# PCB-TLY-JACK-MEGA.net
KiCad netlist of a schematic drawn in EAGLE
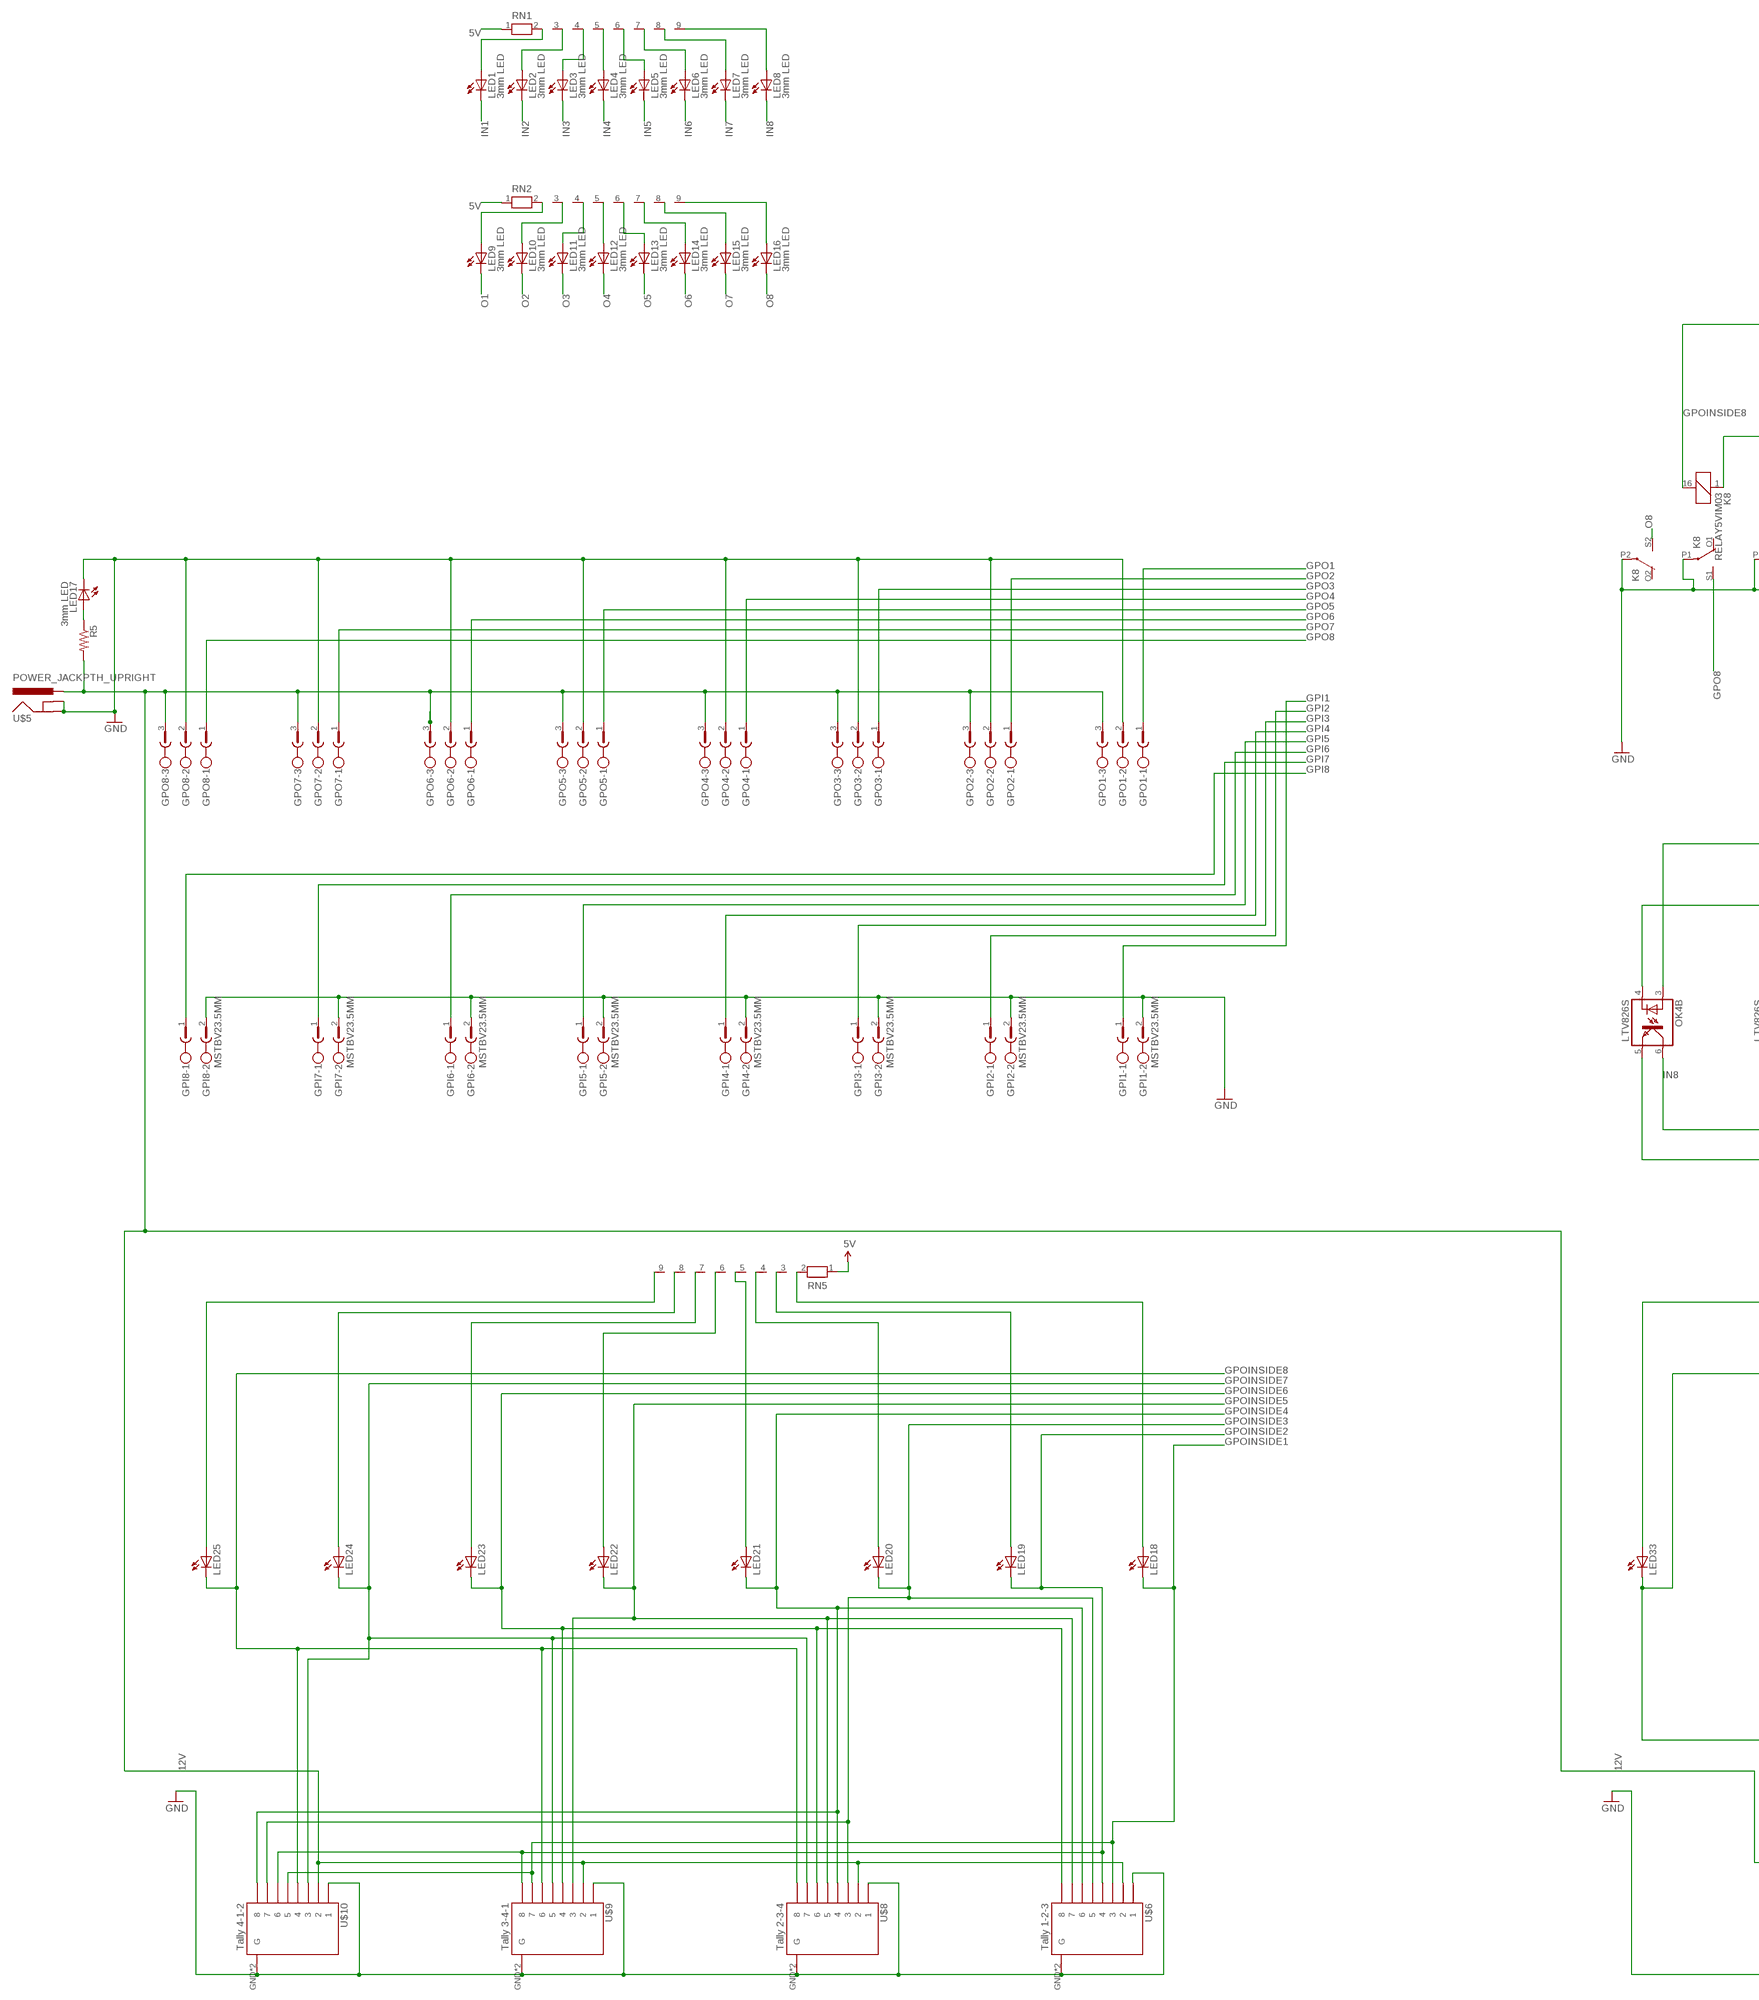
[diagram p0: schematic, sheet 1, part 1 of 2]
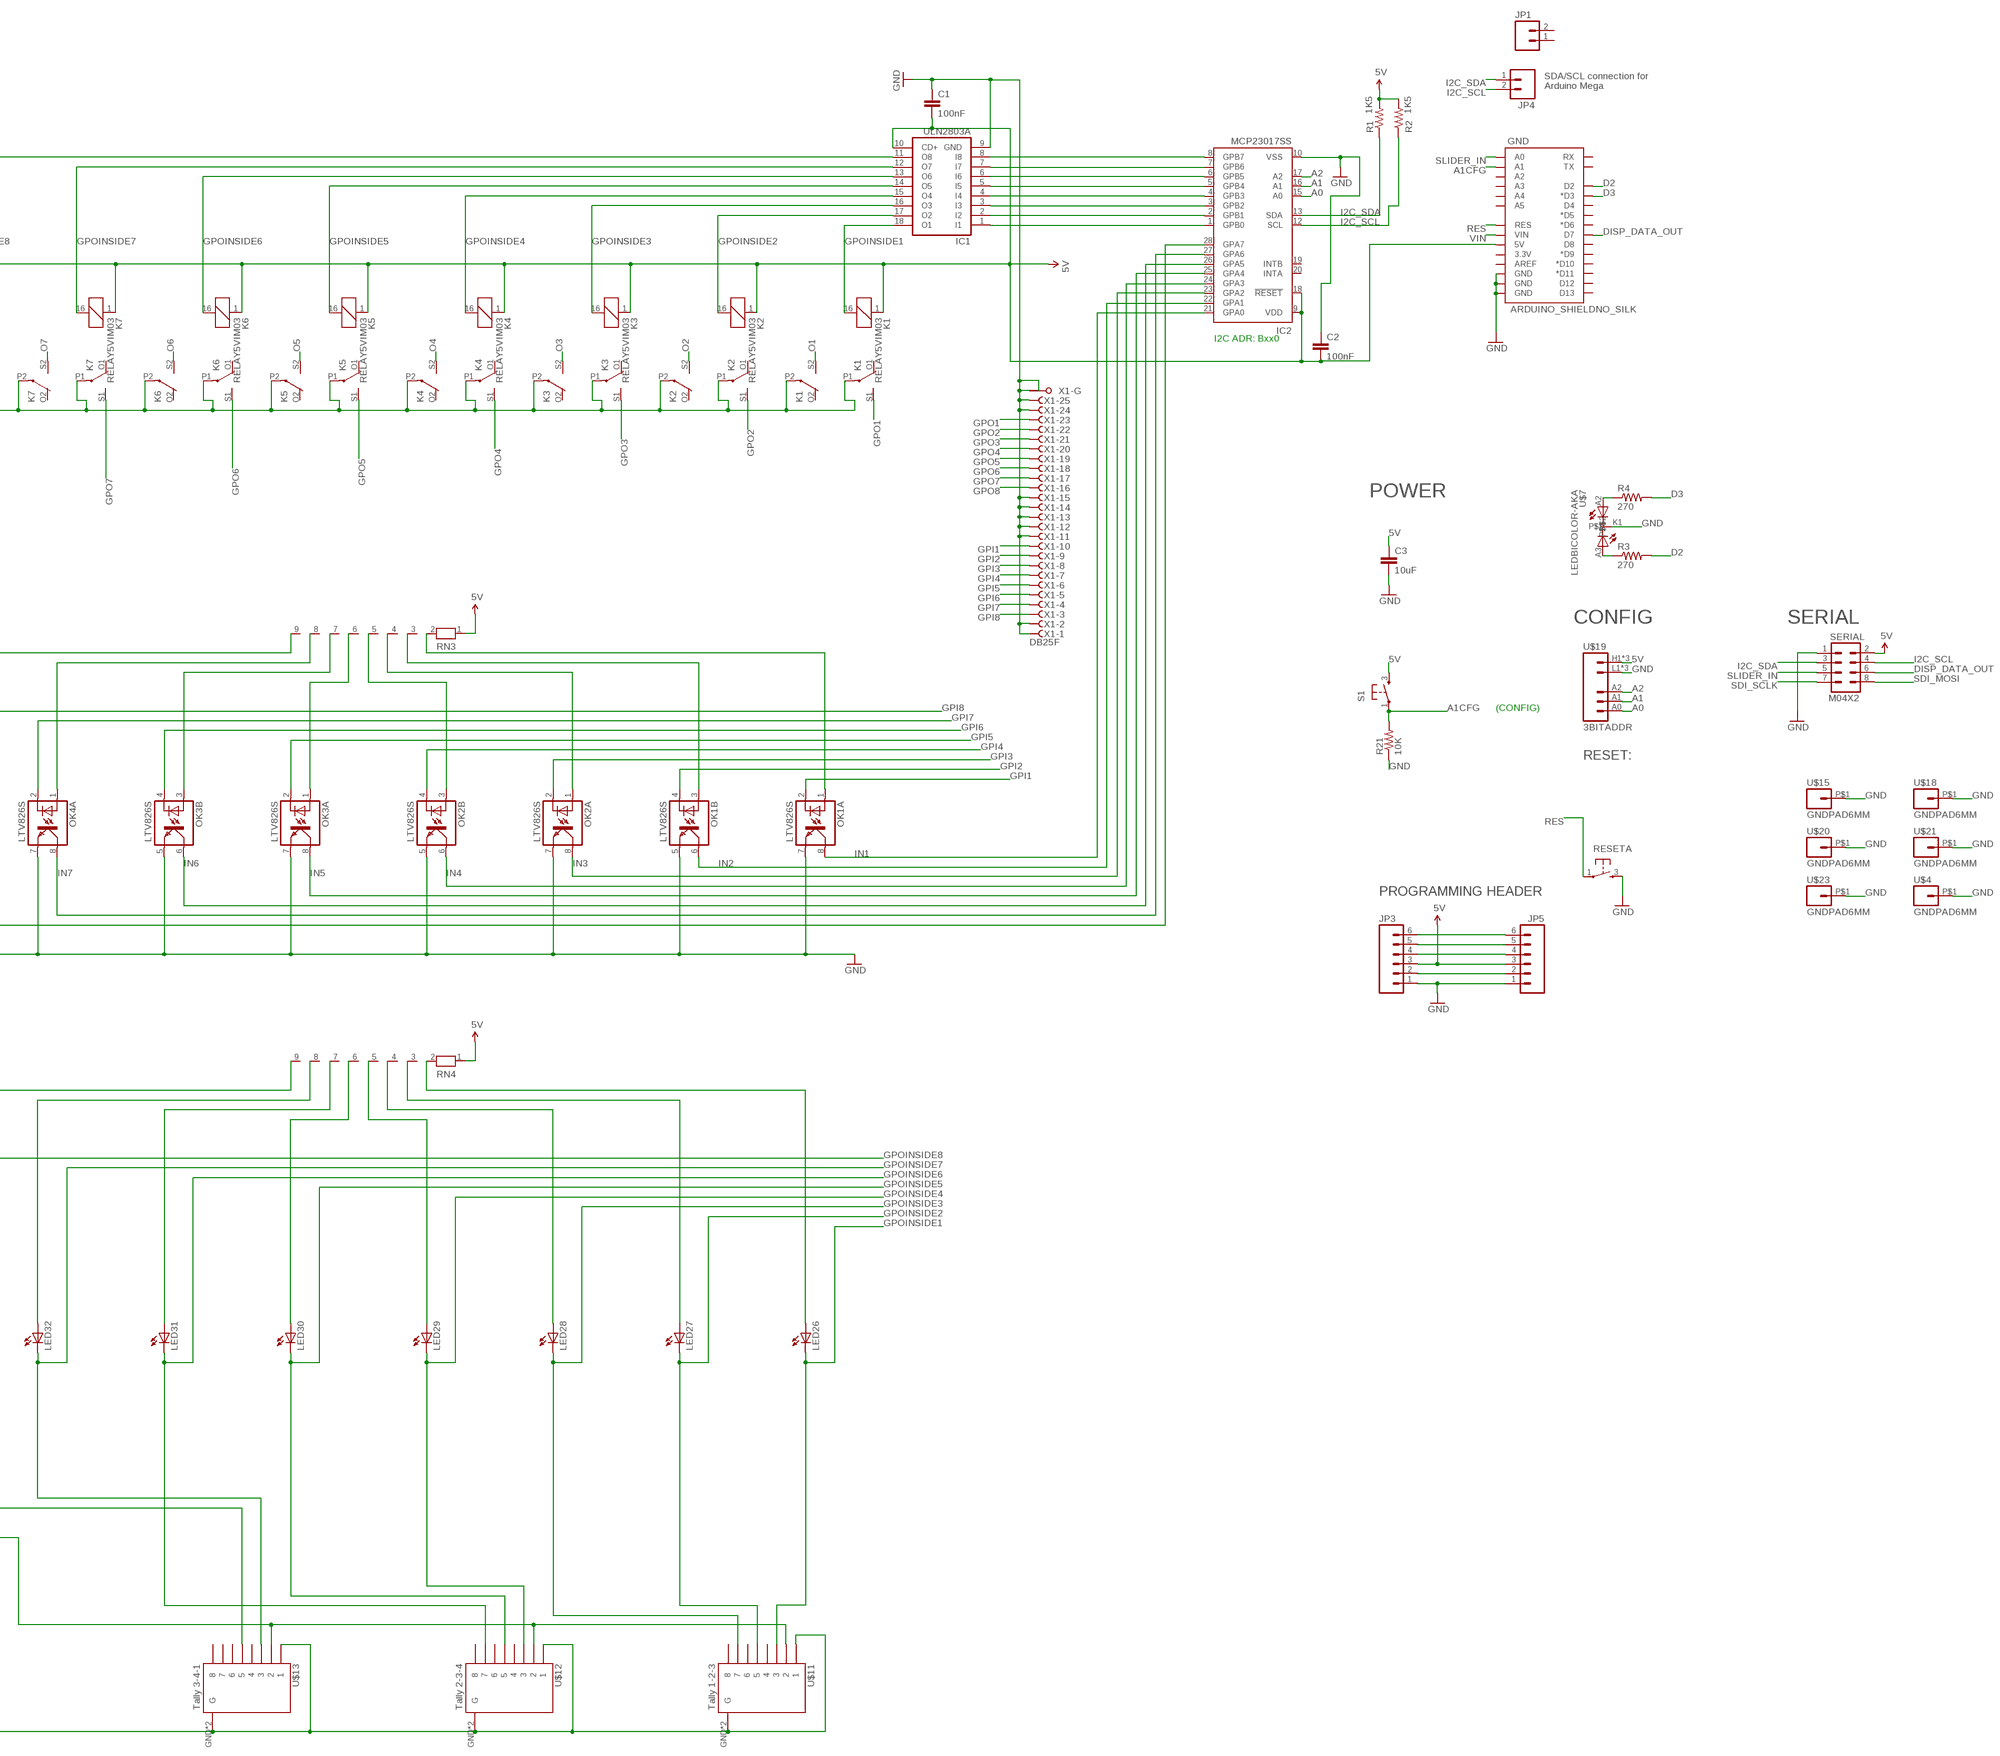
[diagram p1: schematic, sheet 1, part 2 of 2]

(export (version "E")
  (design (tool "Eeschema 10.0.6"))
  (components
    (comp (ref "C1")
      (value "100nF")
      (footprint "eagle-import:0805")
      (libsource (lib "eagle-import") (part "CAP0805"))
    )
    (comp (ref "C2")
      (value "100nF")
      (footprint "eagle-import:0603-CAP")
      (libsource (lib "eagle-import") (part "CAP0603-CAP"))
    )
    (comp (ref "C3")
      (value "10uF")
      (footprint "eagle-import:0805")
      (libsource (lib "eagle-import") (part "CAP0805"))
    )
    (comp (ref "GND")
      (value "ARDUINO_SHIELDNO_SILK")
      (footprint "eagle-import:DUEMILANOVE_VIAS")
      (libsource (lib "eagle-import") (part "ARDUINO_SHIELDNO_SILK"))
    )
    (comp (ref "GPI1")
      (value "MSTBV23.5MM")
      (footprint "eagle-import:MSTBV2-3.5")
      (libsource (lib "eagle-import") (part "MSTBV23.5MM"))
    )
    (comp (ref "GPI2")
      (value "MSTBV23.5MM")
      (footprint "eagle-import:MSTBV2-3.5")
      (libsource (lib "eagle-import") (part "MSTBV23.5MM"))
    )
    (comp (ref "GPI3")
      (value "MSTBV23.5MM")
      (footprint "eagle-import:MSTBV2-3.5")
      (libsource (lib "eagle-import") (part "MSTBV23.5MM"))
    )
    (comp (ref "GPI4")
      (value "MSTBV23.5MM")
      (footprint "eagle-import:MSTBV2-3.5")
      (libsource (lib "eagle-import") (part "MSTBV23.5MM"))
    )
    (comp (ref "GPI5")
      (value "MSTBV23.5MM")
      (footprint "eagle-import:MSTBV2-3.5")
      (libsource (lib "eagle-import") (part "MSTBV23.5MM"))
    )
    (comp (ref "GPI6")
      (value "MSTBV23.5MM")
      (footprint "eagle-import:MSTBV2-3.5")
      (libsource (lib "eagle-import") (part "MSTBV23.5MM"))
    )
    (comp (ref "GPI7")
      (value "MSTBV23.5MM")
      (footprint "eagle-import:MSTBV2-3.5")
      (libsource (lib "eagle-import") (part "MSTBV23.5MM"))
    )
    (comp (ref "GPI8")
      (value "MSTBV23.5MM")
      (footprint "eagle-import:MSTBV2-3.5")
      (libsource (lib "eagle-import") (part "MSTBV23.5MM"))
    )
    (comp (ref "GPO1")
      (value "CON1")
      (footprint "eagle-import:MSTBV3-3.5")
      (libsource (lib "eagle-import") (part "MSTBV33.5MM"))
    )
    (comp (ref "GPO2")
      (value "CON1")
      (footprint "eagle-import:MSTBV3-3.5")
      (libsource (lib "eagle-import") (part "MSTBV33.5MM"))
    )
    (comp (ref "GPO3")
      (value "CON1")
      (footprint "eagle-import:MSTBV3-3.5")
      (libsource (lib "eagle-import") (part "MSTBV33.5MM"))
    )
    (comp (ref "GPO4")
      (value "CON1")
      (footprint "eagle-import:MSTBV3-3.5")
      (libsource (lib "eagle-import") (part "MSTBV33.5MM"))
    )
    (comp (ref "GPO5")
      (value "CON1")
      (footprint "eagle-import:MSTBV3-3.5")
      (libsource (lib "eagle-import") (part "MSTBV33.5MM"))
    )
    (comp (ref "GPO6")
      (value "CON1")
      (footprint "eagle-import:MSTBV3-3.5")
      (libsource (lib "eagle-import") (part "MSTBV33.5MM"))
    )
    (comp (ref "GPO7")
      (value "CON1")
      (footprint "eagle-import:MSTBV3-3.5")
      (libsource (lib "eagle-import") (part "MSTBV33.5MM"))
    )
    (comp (ref "GPO8")
      (value "CON1")
      (footprint "eagle-import:MSTBV3-3.5")
      (libsource (lib "eagle-import") (part "MSTBV33.5MM"))
    )
    (comp (ref "IC1")
      (value "ULN2803A")
      (footprint "eagle-import:SO18W")
      (libsource (lib "eagle-import") (part "ULN2803ASO18W"))
    )
    (comp (ref "IC2")
      (value "MCP23017SS")
      (footprint "eagle-import:SSOP28")
      (fields (field (name "MF") "MICROCHIP") (field (name "MPN") "MCP23017-E/SS"))
      (libsource (lib "eagle-import") (part "MCP23017SS"))
    )
    (comp (ref "JP1")
      (value "M02PTH")
      (footprint "eagle-import:1X02")
      (libsource (lib "eagle-import") (part "M02PTH"))
    )
    (comp (ref "JP3")
      (value "M06POLAR")
      (footprint "eagle-import:MOLEX-1X6")
      (libsource (lib "eagle-import") (part "M06POLAR"))
    )
    (comp (ref "JP4")
      (value "M02PTH")
      (footprint "eagle-import:1X02")
      (libsource (lib "eagle-import") (part "M02PTH"))
    )
    (comp (ref "JP5")
      (value "M06POLAR")
      (footprint "eagle-import:MOLEX-1X6")
      (libsource (lib "eagle-import") (part "M06POLAR"))
    )
    (comp (ref "K1")
      (value "RELAY5VIM03")
      (footprint "eagle-import:DS2Y")
      (libsource (lib "eagle-import") (part "RELAY5VIM03"))
    )
    (comp (ref "K2")
      (value "RELAY5VIM03")
      (footprint "eagle-import:DS2Y")
      (libsource (lib "eagle-import") (part "RELAY5VIM03"))
    )
    (comp (ref "K3")
      (value "RELAY5VIM03")
      (footprint "eagle-import:DS2Y")
      (libsource (lib "eagle-import") (part "RELAY5VIM03"))
    )
    (comp (ref "K4")
      (value "RELAY5VIM03")
      (footprint "eagle-import:DS2Y")
      (libsource (lib "eagle-import") (part "RELAY5VIM03"))
    )
    (comp (ref "K5")
      (value "RELAY5VIM03")
      (footprint "eagle-import:DS2Y")
      (libsource (lib "eagle-import") (part "RELAY5VIM03"))
    )
    (comp (ref "K6")
      (value "RELAY5VIM03")
      (footprint "eagle-import:DS2Y")
      (libsource (lib "eagle-import") (part "RELAY5VIM03"))
    )
    (comp (ref "K7")
      (value "RELAY5VIM03")
      (footprint "eagle-import:DS2Y")
      (libsource (lib "eagle-import") (part "RELAY5VIM03"))
    )
    (comp (ref "K8")
      (value "RELAY5VIM03")
      (footprint "eagle-import:DS2Y")
      (libsource (lib "eagle-import") (part "RELAY5VIM03"))
    )
    (comp (ref "LED1")
      (value "3mm LED")
      (footprint "eagle-import:LED3MM")
      (libsource (lib "eagle-import") (part "LED3MM"))
    )
    (comp (ref "LED2")
      (value "3mm LED")
      (footprint "eagle-import:LED3MM")
      (libsource (lib "eagle-import") (part "LED3MM"))
    )
    (comp (ref "LED3")
      (value "3mm LED")
      (footprint "eagle-import:LED3MM")
      (libsource (lib "eagle-import") (part "LED3MM"))
    )
    (comp (ref "LED4")
      (value "3mm LED")
      (footprint "eagle-import:LED3MM")
      (libsource (lib "eagle-import") (part "LED3MM"))
    )
    (comp (ref "LED5")
      (value "3mm LED")
      (footprint "eagle-import:LED3MM")
      (libsource (lib "eagle-import") (part "LED3MM"))
    )
    (comp (ref "LED6")
      (value "3mm LED")
      (footprint "eagle-import:LED3MM")
      (libsource (lib "eagle-import") (part "LED3MM"))
    )
    (comp (ref "LED7")
      (value "3mm LED")
      (footprint "eagle-import:LED3MM")
      (libsource (lib "eagle-import") (part "LED3MM"))
    )
    (comp (ref "LED8")
      (value "3mm LED")
      (footprint "eagle-import:LED3MM")
      (libsource (lib "eagle-import") (part "LED3MM"))
    )
    (comp (ref "LED9")
      (value "3mm LED")
      (footprint "eagle-import:LED3MM")
      (libsource (lib "eagle-import") (part "LED3MM"))
    )
    (comp (ref "LED10")
      (value "3mm LED")
      (footprint "eagle-import:LED3MM")
      (libsource (lib "eagle-import") (part "LED3MM"))
    )
    (comp (ref "LED11")
      (value "3mm LED")
      (footprint "eagle-import:LED3MM")
      (libsource (lib "eagle-import") (part "LED3MM"))
    )
    (comp (ref "LED12")
      (value "3mm LED")
      (footprint "eagle-import:LED3MM")
      (libsource (lib "eagle-import") (part "LED3MM"))
    )
    (comp (ref "LED13")
      (value "3mm LED")
      (footprint "eagle-import:LED3MM")
      (libsource (lib "eagle-import") (part "LED3MM"))
    )
    (comp (ref "LED14")
      (value "3mm LED")
      (footprint "eagle-import:LED3MM")
      (libsource (lib "eagle-import") (part "LED3MM"))
    )
    (comp (ref "LED15")
      (value "3mm LED")
      (footprint "eagle-import:LED3MM")
      (libsource (lib "eagle-import") (part "LED3MM"))
    )
    (comp (ref "LED16")
      (value "3mm LED")
      (footprint "eagle-import:LED3MM")
      (libsource (lib "eagle-import") (part "LED3MM"))
    )
    (comp (ref "LED17")
      (value "3mm LED")
      (footprint "eagle-import:LED3MM")
      (libsource (lib "eagle-import") (part "LED3MM"))
    )
    (comp (ref "LED18")
      (value "LED3MM")
      (footprint "eagle-import:LED3MM")
      (libsource (lib "eagle-import") (part "led_LED3MM"))
    )
    (comp (ref "LED19")
      (value "LED3MM")
      (footprint "eagle-import:LED3MM")
      (libsource (lib "eagle-import") (part "led_LED3MM"))
    )
    (comp (ref "LED20")
      (value "LED3MM")
      (footprint "eagle-import:LED3MM")
      (libsource (lib "eagle-import") (part "led_LED3MM"))
    )
    (comp (ref "LED21")
      (value "LED3MM")
      (footprint "eagle-import:LED3MM")
      (libsource (lib "eagle-import") (part "led_LED3MM"))
    )
    (comp (ref "LED22")
      (value "LED3MM")
      (footprint "eagle-import:LED3MM")
      (libsource (lib "eagle-import") (part "led_LED3MM"))
    )
    (comp (ref "LED23")
      (value "LED3MM")
      (footprint "eagle-import:LED3MM")
      (libsource (lib "eagle-import") (part "led_LED3MM"))
    )
    (comp (ref "LED24")
      (value "LED3MM")
      (footprint "eagle-import:LED3MM")
      (libsource (lib "eagle-import") (part "led_LED3MM"))
    )
    (comp (ref "LED25")
      (value "LED3MM")
      (footprint "eagle-import:LED3MM")
      (libsource (lib "eagle-import") (part "led_LED3MM"))
    )
    (comp (ref "LED26")
      (value "LED3MM")
      (footprint "eagle-import:LED3MM")
      (libsource (lib "eagle-import") (part "led_LED3MM"))
    )
    (comp (ref "LED27")
      (value "LED3MM")
      (footprint "eagle-import:LED3MM")
      (libsource (lib "eagle-import") (part "led_LED3MM"))
    )
    (comp (ref "LED28")
      (value "LED3MM")
      (footprint "eagle-import:LED3MM")
      (libsource (lib "eagle-import") (part "led_LED3MM"))
    )
    (comp (ref "LED29")
      (value "LED3MM")
      (footprint "eagle-import:LED3MM")
      (libsource (lib "eagle-import") (part "led_LED3MM"))
    )
    (comp (ref "LED30")
      (value "LED3MM")
      (footprint "eagle-import:LED3MM")
      (libsource (lib "eagle-import") (part "led_LED3MM"))
    )
    (comp (ref "LED31")
      (value "LED3MM")
      (footprint "eagle-import:LED3MM")
      (libsource (lib "eagle-import") (part "led_LED3MM"))
    )
    (comp (ref "LED32")
      (value "LED3MM")
      (footprint "eagle-import:LED3MM")
      (libsource (lib "eagle-import") (part "led_LED3MM"))
    )
    (comp (ref "LED33")
      (value "LED3MM")
      (footprint "eagle-import:LED3MM")
      (libsource (lib "eagle-import") (part "led_LED3MM"))
    )
    (comp (ref "OK1")
      (value "LTV826S")
      (footprint "eagle-import:DIL8-SMD")
      (libsource (lib "eagle-import") (part "LTV826S"))
    )
    (comp (ref "OK2")
      (value "LTV826S")
      (footprint "eagle-import:DIL8-SMD")
      (libsource (lib "eagle-import") (part "LTV826S"))
    )
    (comp (ref "OK3")
      (value "LTV826S")
      (footprint "eagle-import:DIL8-SMD")
      (libsource (lib "eagle-import") (part "LTV826S"))
    )
    (comp (ref "OK4")
      (value "LTV826S")
      (footprint "eagle-import:DIL8-SMD")
      (libsource (lib "eagle-import") (part "LTV826S"))
    )
    (comp (ref "R1")
      (value "1K5")
      (footprint "eagle-import:0603-RES")
      (libsource (lib "eagle-import") (part "RESISTOR0603-RES"))
    )
    (comp (ref "R2")
      (value "1K5")
      (footprint "eagle-import:0603-RES")
      (libsource (lib "eagle-import") (part "RESISTOR0603-RES"))
    )
    (comp (ref "R3")
      (value "270")
      (footprint "eagle-import:0603-RES")
      (libsource (lib "eagle-import") (part "RESISTOR0603-RES"))
    )
    (comp (ref "R4")
      (value "270")
      (footprint "eagle-import:0603-RES")
      (libsource (lib "eagle-import") (part "RESISTOR0603-RES"))
    )
    (comp (ref "R5")
      (value "RESISTOR0603-RES")
      (footprint "eagle-import:0603-RES")
      (libsource (lib "eagle-import") (part "RESISTOR0603-RES"))
    )
    (comp (ref "R21")
      (value "10K")
      (footprint "eagle-import:0603-RES")
      (libsource (lib "eagle-import") (part "RESISTOR0603-RES"))
    )
    (comp (ref "RESETA")
      (value "TAC_SWITCH")
      (footprint "eagle-import:PUSHBUTTON")
      (libsource (lib "eagle-import") (part "TAC_SWITCH"))
    )
    (comp (ref "RN1")
      (value "RN08")
      (footprint "eagle-import:RN-9")
      (libsource (lib "eagle-import") (part "RN08"))
    )
    (comp (ref "RN2")
      (value "RN08")
      (footprint "eagle-import:RN-9")
      (libsource (lib "eagle-import") (part "RN08"))
    )
    (comp (ref "RN3")
      (value "RN08")
      (footprint "eagle-import:RN-9")
      (libsource (lib "eagle-import") (part "RN08"))
    )
    (comp (ref "RN4")
      (value "RN08")
      (footprint "eagle-import:RN-9")
      (libsource (lib "eagle-import") (part "RN08"))
    )
    (comp (ref "RN5")
      (value "RN08")
      (footprint "eagle-import:RN-9")
      (libsource (lib "eagle-import") (part "RN08"))
    )
    (comp (ref "S1")
      (value "TAC_SWITCH")
      (footprint "eagle-import:PUSHBUTTON")
      (libsource (lib "eagle-import") (part "TAC_SWITCH"))
    )
    (comp (ref "SERIAL")
      (value "M04X2")
      (footprint "eagle-import:2X4")
      (libsource (lib "eagle-import") (part "M04X2"))
    )
    (comp (ref "U$4")
      (value "GNDPAD6MM")
      (footprint "eagle-import:3.2MMPAD6MM")
      (libsource (lib "eagle-import") (part "GNDPAD6MM"))
    )
    (comp (ref "U$5")
      (value "POWER_JACKPTH_UPRIGHT")
      (footprint "eagle-import:POWER_JACK_PTH_UPRIGHT")
      (libsource (lib "eagle-import") (part "POWER_JACKPTH_UPRIGHT"))
    )
    (comp (ref "U$6")
      (value "Tally 1-2-3")
      (footprint "eagle-import:RJ45-8_GND_UPRIGHT")
      (libsource (lib "eagle-import") (part "RJ45-8_GNDUPRIGHT"))
    )
    (comp (ref "U$7")
      (value "LEDBICOLOR-AKA")
      (footprint "eagle-import:LED5MM-BICOLOR")
      (libsource (lib "eagle-import") (part "LEDBICOLOR-AKA"))
    )
    (comp (ref "U$8")
      (value "Tally 2-3-4")
      (footprint "eagle-import:RJ45-8_GND_UPRIGHT")
      (libsource (lib "eagle-import") (part "RJ45-8_GNDUPRIGHT"))
    )
    (comp (ref "U$9")
      (value "Tally 3-4-1")
      (footprint "eagle-import:RJ45-8_GND_UPRIGHT")
      (libsource (lib "eagle-import") (part "RJ45-8_GNDUPRIGHT"))
    )
    (comp (ref "U$10")
      (value "Tally 4-1-2")
      (footprint "eagle-import:RJ45-8_GND_UPRIGHT")
      (libsource (lib "eagle-import") (part "RJ45-8_GNDUPRIGHT"))
    )
    (comp (ref "U$11")
      (value "Tally 1-2-3")
      (footprint "eagle-import:RJ45-8_GND_UPRIGHT")
      (libsource (lib "eagle-import") (part "RJ45-8_GNDUPRIGHT"))
    )
    (comp (ref "U$12")
      (value "Tally 2-3-4")
      (footprint "eagle-import:RJ45-8_GND_UPRIGHT")
      (libsource (lib "eagle-import") (part "RJ45-8_GNDUPRIGHT"))
    )
    (comp (ref "U$13")
      (value "Tally 3-4-1")
      (footprint "eagle-import:RJ45-8_GND_UPRIGHT")
      (libsource (lib "eagle-import") (part "RJ45-8_GNDUPRIGHT"))
    )
    (comp (ref "U$15")
      (value "GNDPAD6MM")
      (footprint "eagle-import:3.2MMPAD6MM")
      (libsource (lib "eagle-import") (part "GNDPAD6MM"))
    )
    (comp (ref "U$18")
      (value "GNDPAD6MM")
      (footprint "eagle-import:3.2MMPAD6MM")
      (libsource (lib "eagle-import") (part "GNDPAD6MM"))
    )
    (comp (ref "U$19")
      (value "3BITADDR")
      (footprint "eagle-import:3BITADDR")
      (libsource (lib "eagle-import") (part "3BITADDR"))
    )
    (comp (ref "U$20")
      (value "GNDPAD6MM")
      (footprint "eagle-import:3.2MMPAD6MM")
      (libsource (lib "eagle-import") (part "GNDPAD6MM"))
    )
    (comp (ref "U$21")
      (value "GNDPAD6MM")
      (footprint "eagle-import:3.2MMPAD6MM")
      (libsource (lib "eagle-import") (part "GNDPAD6MM"))
    )
    (comp (ref "U$23")
      (value "GNDPAD6MM")
      (footprint "eagle-import:3.2MMPAD6MM")
      (libsource (lib "eagle-import") (part "GNDPAD6MM"))
    )
    (comp (ref "X1")
      (value "DB25F")
      (footprint "eagle-import:F25HP")
      (libsource (lib "eagle-import") (part "F25HPS"))
    )
  )
  (nets
    (net (code "1") (name "5V") (class "Default")
      (node (ref "C1") (pin "2") (pinfunction "2_2") (pintype "passive"))
      (node (ref "C2") (pin "2") (pinfunction "2_2") (pintype "passive"))
      (node (ref "C3") (pin "1") (pinfunction "1_1") (pintype "passive"))
      (node (ref "GND") (pin "5V") (pinfunction "5V_5V") (pintype "bidirectional"))
      (node (ref "IC1") (pin "10") (pinfunction "CD+_10") (pintype "passive"))
      (node (ref "IC2") (pin "18") (pinfunction "~{RESET}_18") (pintype "input"))
      (node (ref "IC2") (pin "9") (pinfunction "VDD_9") (pintype "power_in"))
      (node (ref "JP3") (pin "3") (pinfunction "3_3") (pintype "passive"))
      (node (ref "JP5") (pin "3") (pinfunction "3_3") (pintype "passive"))
      (node (ref "K1") (pin "1") (pinfunction "1_1") (pintype "passive"))
      (node (ref "K2") (pin "1") (pinfunction "1_1") (pintype "passive"))
      (node (ref "K3") (pin "1") (pinfunction "1_1") (pintype "passive"))
      (node (ref "K4") (pin "1") (pinfunction "1_1") (pintype "passive"))
      (node (ref "K5") (pin "1") (pinfunction "1_1") (pintype "passive"))
      (node (ref "K6") (pin "1") (pinfunction "1_1") (pintype "passive"))
      (node (ref "K7") (pin "1") (pinfunction "1_1") (pintype "passive"))
      (node (ref "K8") (pin "1") (pinfunction "1_1") (pintype "passive"))
      (node (ref "R1") (pin "2") (pinfunction "2_2") (pintype "passive"))
      (node (ref "R2") (pin "2") (pinfunction "2_2") (pintype "passive"))
      (node (ref "RN1") (pin "1") (pinfunction "1_1") (pintype "passive"))
      (node (ref "RN2") (pin "1") (pinfunction "1_1") (pintype "passive"))
      (node (ref "RN3") (pin "1") (pinfunction "1_1") (pintype "passive"))
      (node (ref "RN4") (pin "1") (pinfunction "1_1") (pintype "passive"))
      (node (ref "RN5") (pin "1") (pinfunction "1_1") (pintype "passive"))
      (node (ref "S1") (pin "3") (pinfunction "3_3") (pintype "passive"))
      (node (ref "SERIAL") (pin "2") (pinfunction "2_2") (pintype "passive"))
      (node (ref "U$19") (pin "H1") (pinfunction "VCC_H1") (pintype "passive"))
      (node (ref "U$19") (pin "H2") (pinfunction "VCC_H2") (pintype "passive"))
      (node (ref "U$19") (pin "H3") (pinfunction "VCC_H3") (pintype "passive"))
    )
    (net (code "2") (name "12V") (class "Default")
      (node (ref "GPO1") (pin "3") (pinfunction "1_3") (pintype "passive"))
      (node (ref "GPO2") (pin "3") (pinfunction "1_3") (pintype "passive"))
      (node (ref "GPO3") (pin "3") (pinfunction "1_3") (pintype "passive"))
      (node (ref "GPO4") (pin "3") (pinfunction "1_3") (pintype "passive"))
      (node (ref "GPO5") (pin "3") (pinfunction "1_3") (pintype "passive"))
      (node (ref "GPO6") (pin "3") (pinfunction "1_3") (pintype "passive"))
      (node (ref "GPO7") (pin "3") (pinfunction "1_3") (pintype "passive"))
      (node (ref "GPO8") (pin "3") (pinfunction "1_3") (pintype "passive"))
      (node (ref "R5") (pin "2") (pinfunction "2_2") (pintype "passive"))
      (node (ref "U$10") (pin "2") (pinfunction "2_2") (pintype "bidirectional"))
      (node (ref "U$11") (pin "2") (pinfunction "2_2") (pintype "bidirectional"))
      (node (ref "U$12") (pin "2") (pinfunction "2_2") (pintype "bidirectional"))
      (node (ref "U$13") (pin "2") (pinfunction "2_2") (pintype "bidirectional"))
      (node (ref "U$5") (pin "PWR") (pinfunction "PWR_PWR") (pintype "bidirectional"))
      (node (ref "U$6") (pin "2") (pinfunction "2_2") (pintype "bidirectional"))
      (node (ref "U$8") (pin "2") (pinfunction "2_2") (pintype "bidirectional"))
      (node (ref "U$9") (pin "2") (pinfunction "2_2") (pintype "bidirectional"))
    )
    (net (code "3") (name "A0") (class "Default")
      (node (ref "IC2") (pin "15") (pinfunction "A0_15") (pintype "input"))
      (node (ref "U$19") (pin "A0") (pinfunction "A0_A0") (pintype "passive"))
    )
    (net (code "4") (name "A1") (class "Default")
      (node (ref "IC2") (pin "16") (pinfunction "A1_16") (pintype "input"))
      (node (ref "U$19") (pin "A1") (pinfunction "A1_A1") (pintype "passive"))
    )
    (net (code "5") (name "A1CFG") (class "Default")
      (node (ref "GND") (pin "A1") (pinfunction "A1_A1") (pintype "bidirectional"))
      (node (ref "R21") (pin "2") (pinfunction "2_2") (pintype "passive"))
      (node (ref "S1") (pin "1") (pinfunction "1_1") (pintype "passive"))
    )
    (net (code "6") (name "A2") (class "Default")
      (node (ref "IC2") (pin "17") (pinfunction "A2_17") (pintype "input"))
      (node (ref "U$19") (pin "A2") (pinfunction "A2_A2") (pintype "passive"))
    )
    (net (code "7") (name "D2") (class "Default")
      (node (ref "GND") (pin "D2") (pinfunction "D2_D2") (pintype "bidirectional"))
      (node (ref "R3") (pin "2") (pinfunction "2_2") (pintype "passive"))
    )
    (net (code "8") (name "D3") (class "Default")
      (node (ref "GND") (pin "D3") (pinfunction "*D3_D3") (pintype "bidirectional"))
      (node (ref "R4") (pin "2") (pinfunction "2_2") (pintype "passive"))
    )
    (net (code "9") (name "DISP_DATA_OUT") (class "Default")
      (node (ref "GND") (pin "D7") (pinfunction "D7_D7") (pintype "bidirectional"))
      (node (ref "SERIAL") (pin "6") (pinfunction "6_6") (pintype "passive"))
    )
    (net (code "10") (name "GND") (class "Default")
      (node (ref "C1") (pin "1") (pinfunction "1_1") (pintype "passive"))
      (node (ref "C2") (pin "1") (pinfunction "1_1") (pintype "passive"))
      (node (ref "C3") (pin "2") (pinfunction "2_2") (pintype "passive"))
      (node (ref "GND") (pin "GND@0") (pinfunction "GND_GND@0") (pintype "bidirectional"))
      (node (ref "GND") (pin "GND@1") (pinfunction "GND_GND@1") (pintype "bidirectional"))
      (node (ref "GND") (pin "GND@2") (pinfunction "GND_GND@2") (pintype "bidirectional"))
      (node (ref "GPI1") (pin "2") (pinfunction "1_2") (pintype "passive"))
      (node (ref "GPI2") (pin "2") (pinfunction "1_2") (pintype "passive"))
      (node (ref "GPI3") (pin "2") (pinfunction "1_2") (pintype "passive"))
      (node (ref "GPI4") (pin "2") (pinfunction "1_2") (pintype "passive"))
      (node (ref "GPI5") (pin "2") (pinfunction "1_2") (pintype "passive"))
      (node (ref "GPI6") (pin "2") (pinfunction "1_2") (pintype "passive"))
      (node (ref "GPI7") (pin "2") (pinfunction "1_2") (pintype "passive"))
      (node (ref "GPI8") (pin "2") (pinfunction "1_2") (pintype "passive"))
      (node (ref "GPO1") (pin "2") (pinfunction "1_2") (pintype "passive"))
      (node (ref "GPO2") (pin "2") (pinfunction "1_2") (pintype "passive"))
      (node (ref "GPO3") (pin "2") (pinfunction "1_2") (pintype "passive"))
      (node (ref "GPO4") (pin "2") (pinfunction "1_2") (pintype "passive"))
      (node (ref "GPO5") (pin "2") (pinfunction "1_2") (pintype "passive"))
      (node (ref "GPO6") (pin "2") (pinfunction "1_2") (pintype "passive"))
      (node (ref "GPO7") (pin "2") (pinfunction "1_2") (pintype "passive"))
      (node (ref "GPO8") (pin "2") (pinfunction "1_2") (pintype "passive"))
      (node (ref "IC1") (pin "9") (pinfunction "GND_9") (pintype "power_in"))
      (node (ref "IC2") (pin "10") (pinfunction "VSS_10") (pintype "power_in"))
      (node (ref "JP3") (pin "1") (pinfunction "1_1") (pintype "passive"))
      (node (ref "JP5") (pin "1") (pinfunction "1_1") (pintype "passive"))
      (node (ref "K1") (pin "P1") (pinfunction "P_P1") (pintype "passive"))
      (node (ref "K1") (pin "P2") (pinfunction "P_P2") (pintype "passive"))
      (node (ref "K2") (pin "P1") (pinfunction "P_P1") (pintype "passive"))
      (node (ref "K2") (pin "P2") (pinfunction "P_P2") (pintype "passive"))
      (node (ref "K3") (pin "P1") (pinfunction "P_P1") (pintype "passive"))
      (node (ref "K3") (pin "P2") (pinfunction "P_P2") (pintype "passive"))
      (node (ref "K4") (pin "P1") (pinfunction "P_P1") (pintype "passive"))
      (node (ref "K4") (pin "P2") (pinfunction "P_P2") (pintype "passive"))
      (node (ref "K5") (pin "P1") (pinfunction "P_P1") (pintype "passive"))
      (node (ref "K5") (pin "P2") (pinfunction "P_P2") (pintype "passive"))
      (node (ref "K6") (pin "P1") (pinfunction "P_P1") (pintype "passive"))
      (node (ref "K6") (pin "P2") (pinfunction "P_P2") (pintype "passive"))
      (node (ref "K7") (pin "P1") (pinfunction "P_P1") (pintype "passive"))
      (node (ref "K7") (pin "P2") (pinfunction "P_P2") (pintype "passive"))
      (node (ref "K8") (pin "P1") (pinfunction "P_P1") (pintype "passive"))
      (node (ref "K8") (pin "P2") (pinfunction "P_P2") (pintype "passive"))
      (node (ref "LED17") (pin "K") (pinfunction "C_K") (pintype "passive"))
      (node (ref "OK1") (pin "5") (pinfunction "EMIT_5") (pintype "passive"))
      (node (ref "OK1") (pin "7") (pinfunction "EMIT_7") (pintype "passive"))
      (node (ref "OK2") (pin "5") (pinfunction "EMIT_5") (pintype "passive"))
      (node (ref "OK2") (pin "7") (pinfunction "EMIT_7") (pintype "passive"))
      (node (ref "OK3") (pin "5") (pinfunction "EMIT_5") (pintype "passive"))
      (node (ref "OK3") (pin "7") (pinfunction "EMIT_7") (pintype "passive"))
      (node (ref "OK4") (pin "5") (pinfunction "EMIT_5") (pintype "passive"))
      (node (ref "OK4") (pin "7") (pinfunction "EMIT_7") (pintype "passive"))
      (node (ref "R21") (pin "1") (pinfunction "1_1") (pintype "passive"))
      (node (ref "RESETA") (pin "3") (pinfunction "3_3") (pintype "passive"))
      (node (ref "SERIAL") (pin "1") (pinfunction "1_1") (pintype "passive"))
      (node (ref "U$10") (pin "1") (pinfunction "1_1") (pintype "bidirectional"))
      (node (ref "U$10") (pin "GND") (pinfunction "G_GND") (pintype "power_in"))
      (node (ref "U$10") (pin "GND1") (pinfunction "G_GND1") (pintype "power_in"))
      (node (ref "U$11") (pin "1") (pinfunction "1_1") (pintype "bidirectional"))
      (node (ref "U$11") (pin "GND") (pinfunction "G_GND") (pintype "power_in"))
      (node (ref "U$11") (pin "GND1") (pinfunction "G_GND1") (pintype "power_in"))
      (node (ref "U$12") (pin "1") (pinfunction "1_1") (pintype "bidirectional"))
      (node (ref "U$12") (pin "GND") (pinfunction "G_GND") (pintype "power_in"))
      (node (ref "U$12") (pin "GND1") (pinfunction "G_GND1") (pintype "power_in"))
      (node (ref "U$13") (pin "1") (pinfunction "1_1") (pintype "bidirectional"))
      (node (ref "U$13") (pin "GND") (pinfunction "G_GND") (pintype "power_in"))
      (node (ref "U$13") (pin "GND1") (pinfunction "G_GND1") (pintype "power_in"))
      (node (ref "U$15") (pin "P$1") (pinfunction "1_P$1") (pintype "passive"))
      (node (ref "U$18") (pin "P$1") (pinfunction "1_P$1") (pintype "passive"))
      (node (ref "U$19") (pin "L1") (pinfunction "GND_L1") (pintype "passive"))
      (node (ref "U$19") (pin "L2") (pinfunction "GND_L2") (pintype "passive"))
      (node (ref "U$19") (pin "L3") (pinfunction "GND_L3") (pintype "passive"))
      (node (ref "U$20") (pin "P$1") (pinfunction "1_P$1") (pintype "passive"))
      (node (ref "U$21") (pin "P$1") (pinfunction "1_P$1") (pintype "passive"))
      (node (ref "U$23") (pin "P$1") (pinfunction "1_P$1") (pintype "passive"))
      (node (ref "U$4") (pin "P$1") (pinfunction "1_P$1") (pintype "passive"))
      (node (ref "U$5") (pin "GND") (pinfunction "GND_GND") (pintype "bidirectional"))
      (node (ref "U$5") (pin "SHUNT") (pinfunction "GNDBREAK_SHUNT") (pintype "bidirectional"))
      (node (ref "U$6") (pin "1") (pinfunction "1_1") (pintype "bidirectional"))
      (node (ref "U$6") (pin "GND") (pinfunction "G_GND") (pintype "power_in"))
      (node (ref "U$6") (pin "GND1") (pinfunction "G_GND1") (pintype "power_in"))
      (node (ref "U$7") (pin "K1") (pinfunction "P$1_K1") (pintype "bidirectional"))
      (node (ref "U$8") (pin "1") (pinfunction "1_1") (pintype "bidirectional"))
      (node (ref "U$8") (pin "GND") (pinfunction "G_GND") (pintype "power_in"))
      (node (ref "U$8") (pin "GND1") (pinfunction "G_GND1") (pintype "power_in"))
      (node (ref "U$9") (pin "1") (pinfunction "1_1") (pintype "bidirectional"))
      (node (ref "U$9") (pin "GND") (pinfunction "G_GND") (pintype "power_in"))
      (node (ref "U$9") (pin "GND1") (pinfunction "G_GND1") (pintype "power_in"))
      (node (ref "X1") (pin "1") (pinfunction "F_1") (pintype "passive"))
      (node (ref "X1") (pin "11") (pinfunction "F_11") (pintype "passive"))
      (node (ref "X1") (pin "12") (pinfunction "F_12") (pintype "passive"))
      (node (ref "X1") (pin "13") (pinfunction "F_13") (pintype "passive"))
      (node (ref "X1") (pin "14") (pinfunction "F_14") (pintype "passive"))
      (node (ref "X1") (pin "15") (pinfunction "F_15") (pintype "passive"))
      (node (ref "X1") (pin "2") (pinfunction "F_2") (pintype "passive"))
      (node (ref "X1") (pin "24") (pinfunction "F_24") (pintype "passive"))
      (node (ref "X1") (pin "25") (pinfunction "F_25") (pintype "passive"))
      (node (ref "X1") (pin "G1") (pinfunction "G1_G1") (pintype "passive"))
      (node (ref "X1") (pin "G2") (pinfunction "G2_G2") (pintype "passive"))
    )
    (net (code "11") (name "GPI1") (class "Default")
      (node (ref "GPI1") (pin "1") (pinfunction "1_1") (pintype "passive"))
      (node (ref "OK1") (pin "2") (pinfunction "C_2") (pintype "passive"))
      (node (ref "X1") (pin "10") (pinfunction "F_10") (pintype "passive"))
    )
    (net (code "12") (name "GPI2") (class "Default")
      (node (ref "GPI2") (pin "1") (pinfunction "1_1") (pintype "passive"))
      (node (ref "OK1") (pin "4") (pinfunction "C_4") (pintype "passive"))
      (node (ref "X1") (pin "9") (pinfunction "F_9") (pintype "passive"))
    )
    (net (code "13") (name "GPI3") (class "Default")
      (node (ref "GPI3") (pin "1") (pinfunction "1_1") (pintype "passive"))
      (node (ref "OK2") (pin "2") (pinfunction "C_2") (pintype "passive"))
      (node (ref "X1") (pin "8") (pinfunction "F_8") (pintype "passive"))
    )
    (net (code "14") (name "GPI4") (class "Default")
      (node (ref "GPI4") (pin "1") (pinfunction "1_1") (pintype "passive"))
      (node (ref "OK2") (pin "4") (pinfunction "C_4") (pintype "passive"))
      (node (ref "X1") (pin "7") (pinfunction "F_7") (pintype "passive"))
    )
    (net (code "15") (name "GPI5") (class "Default")
      (node (ref "GPI5") (pin "1") (pinfunction "1_1") (pintype "passive"))
      (node (ref "OK3") (pin "2") (pinfunction "C_2") (pintype "passive"))
      (node (ref "X1") (pin "6") (pinfunction "F_6") (pintype "passive"))
    )
    (net (code "16") (name "GPI6") (class "Default")
      (node (ref "GPI6") (pin "1") (pinfunction "1_1") (pintype "passive"))
      (node (ref "OK3") (pin "4") (pinfunction "C_4") (pintype "passive"))
      (node (ref "X1") (pin "5") (pinfunction "F_5") (pintype "passive"))
    )
    (net (code "17") (name "GPI7") (class "Default")
      (node (ref "GPI7") (pin "1") (pinfunction "1_1") (pintype "passive"))
      (node (ref "OK4") (pin "2") (pinfunction "C_2") (pintype "passive"))
      (node (ref "X1") (pin "4") (pinfunction "F_4") (pintype "passive"))
    )
    (net (code "18") (name "GPI8") (class "Default")
      (node (ref "GPI8") (pin "1") (pinfunction "1_1") (pintype "passive"))
      (node (ref "OK4") (pin "4") (pinfunction "C_4") (pintype "passive"))
      (node (ref "X1") (pin "3") (pinfunction "F_3") (pintype "passive"))
    )
    (net (code "19") (name "GPO1") (class "Default")
      (node (ref "GPO1") (pin "1") (pinfunction "1_1") (pintype "passive"))
      (node (ref "K1") (pin "S1") (pinfunction "S_S1") (pintype "passive"))
      (node (ref "X1") (pin "23") (pinfunction "F_23") (pintype "passive"))
    )
    (net (code "20") (name "GPO2") (class "Default")
      (node (ref "GPO2") (pin "1") (pinfunction "1_1") (pintype "passive"))
      (node (ref "K2") (pin "S1") (pinfunction "S_S1") (pintype "passive"))
      (node (ref "X1") (pin "22") (pinfunction "F_22") (pintype "passive"))
    )
    (net (code "21") (name "GPO3") (class "Default")
      (node (ref "GPO3") (pin "1") (pinfunction "1_1") (pintype "passive"))
      (node (ref "K3") (pin "S1") (pinfunction "S_S1") (pintype "passive"))
      (node (ref "X1") (pin "21") (pinfunction "F_21") (pintype "passive"))
    )
    (net (code "22") (name "GPO4") (class "Default")
      (node (ref "GPO4") (pin "1") (pinfunction "1_1") (pintype "passive"))
      (node (ref "K4") (pin "S1") (pinfunction "S_S1") (pintype "passive"))
      (node (ref "X1") (pin "20") (pinfunction "F_20") (pintype "passive"))
    )
    (net (code "23") (name "GPO5") (class "Default")
      (node (ref "GPO5") (pin "1") (pinfunction "1_1") (pintype "passive"))
      (node (ref "K5") (pin "S1") (pinfunction "S_S1") (pintype "passive"))
      (node (ref "X1") (pin "19") (pinfunction "F_19") (pintype "passive"))
    )
    (net (code "24") (name "GPO6") (class "Default")
      (node (ref "GPO6") (pin "1") (pinfunction "1_1") (pintype "passive"))
      (node (ref "K6") (pin "S1") (pinfunction "S_S1") (pintype "passive"))
      (node (ref "X1") (pin "18") (pinfunction "F_18") (pintype "passive"))
    )
    (net (code "25") (name "GPO7") (class "Default")
      (node (ref "GPO7") (pin "1") (pinfunction "1_1") (pintype "passive"))
      (node (ref "K7") (pin "S1") (pinfunction "S_S1") (pintype "passive"))
      (node (ref "X1") (pin "17") (pinfunction "F_17") (pintype "passive"))
    )
    (net (code "26") (name "GPO8") (class "Default")
      (node (ref "GPO8") (pin "1") (pinfunction "1_1") (pintype "passive"))
      (node (ref "K8") (pin "S1") (pinfunction "S_S1") (pintype "passive"))
      (node (ref "X1") (pin "16") (pinfunction "F_16") (pintype "passive"))
    )
    (net (code "27") (name "GPOINSIDE1") (class "Default")
      (node (ref "IC1") (pin "18") (pinfunction "O1_18") (pintype "open_collector"))
      (node (ref "K1") (pin "16") (pinfunction "2_16") (pintype "passive"))
      (node (ref "LED18") (pin "K") (pinfunction "C_K") (pintype "passive"))
      (node (ref "LED26") (pin "K") (pinfunction "C_K") (pintype "passive"))
      (node (ref "U$10") (pin "5") (pinfunction "5_5") (pintype "bidirectional"))
      (node (ref "U$11") (pin "3") (pinfunction "3_3") (pintype "bidirectional"))
      (node (ref "U$6") (pin "3") (pinfunction "3_3") (pintype "bidirectional"))
      (node (ref "U$9") (pin "7") (pinfunction "7_7") (pintype "bidirectional"))
    )
    (net (code "28") (name "GPOINSIDE2") (class "Default")
      (node (ref "IC1") (pin "17") (pinfunction "O2_17") (pintype "open_collector"))
      (node (ref "K2") (pin "16") (pinfunction "2_16") (pintype "passive"))
      (node (ref "LED19") (pin "K") (pinfunction "C_K") (pintype "passive"))
      (node (ref "LED27") (pin "K") (pinfunction "C_K") (pintype "passive"))
      (node (ref "U$10") (pin "6") (pinfunction "6_6") (pintype "bidirectional"))
      (node (ref "U$11") (pin "5") (pinfunction "5_5") (pintype "bidirectional"))
      (node (ref "U$6") (pin "4") (pinfunction "4_4") (pintype "bidirectional"))
      (node (ref "U$9") (pin "8") (pinfunction "8_8") (pintype "bidirectional"))
    )
    (net (code "29") (name "GPOINSIDE3") (class "Default")
      (node (ref "IC1") (pin "16") (pinfunction "O3_16") (pintype "open_collector"))
      (node (ref "K3") (pin "16") (pinfunction "2_16") (pintype "passive"))
      (node (ref "LED20") (pin "K") (pinfunction "C_K") (pintype "passive"))
      (node (ref "LED28") (pin "K") (pinfunction "C_K") (pintype "passive"))
      (node (ref "U$10") (pin "7") (pinfunction "7_7") (pintype "bidirectional"))
      (node (ref "U$11") (pin "7") (pinfunction "7_7") (pintype "bidirectional"))
      (node (ref "U$6") (pin "5") (pinfunction "5_5") (pintype "bidirectional"))
      (node (ref "U$8") (pin "3") (pinfunction "3_3") (pintype "bidirectional"))
    )
    (net (code "30") (name "GPOINSIDE4") (class "Default")
      (node (ref "IC1") (pin "15") (pinfunction "O4_15") (pintype "open_collector"))
      (node (ref "K4") (pin "16") (pinfunction "2_16") (pintype "passive"))
      (node (ref "LED21") (pin "K") (pinfunction "C_K") (pintype "passive"))
      (node (ref "LED29") (pin "K") (pinfunction "C_K") (pintype "passive"))
      (node (ref "U$10") (pin "8") (pinfunction "8_8") (pintype "bidirectional"))
      (node (ref "U$12") (pin "3") (pinfunction "3_3") (pintype "bidirectional"))
      (node (ref "U$6") (pin "6") (pinfunction "6_6") (pintype "bidirectional"))
      (node (ref "U$8") (pin "4") (pinfunction "4_4") (pintype "bidirectional"))
    )
    (net (code "31") (name "GPOINSIDE5") (class "Default")
      (node (ref "IC1") (pin "14") (pinfunction "O5_14") (pintype "open_collector"))
      (node (ref "K5") (pin "16") (pinfunction "2_16") (pintype "passive"))
      (node (ref "LED22") (pin "K") (pinfunction "C_K") (pintype "passive"))
      (node (ref "LED30") (pin "K") (pinfunction "C_K") (pintype "passive"))
      (node (ref "U$12") (pin "5") (pinfunction "5_5") (pintype "bidirectional"))
      (node (ref "U$6") (pin "7") (pinfunction "7_7") (pintype "bidirectional"))
      (node (ref "U$8") (pin "5") (pinfunction "5_5") (pintype "bidirectional"))
      (node (ref "U$9") (pin "3") (pinfunction "3_3") (pintype "bidirectional"))
    )
    (net (code "32") (name "GPOINSIDE6") (class "Default")
      (node (ref "IC1") (pin "13") (pinfunction "O6_13") (pintype "open_collector"))
      (node (ref "K6") (pin "16") (pinfunction "2_16") (pintype "passive"))
      (node (ref "LED23") (pin "K") (pinfunction "C_K") (pintype "passive"))
      (node (ref "LED31") (pin "K") (pinfunction "C_K") (pintype "passive"))
      (node (ref "U$12") (pin "7") (pinfunction "7_7") (pintype "bidirectional"))
      (node (ref "U$6") (pin "8") (pinfunction "8_8") (pintype "bidirectional"))
      (node (ref "U$8") (pin "6") (pinfunction "6_6") (pintype "bidirectional"))
      (node (ref "U$9") (pin "4") (pinfunction "4_4") (pintype "bidirectional"))
    )
    (net (code "33") (name "GPOINSIDE7") (class "Default")
      (node (ref "IC1") (pin "12") (pinfunction "O7_12") (pintype "open_collector"))
      (node (ref "K7") (pin "16") (pinfunction "2_16") (pintype "passive"))
      (node (ref "LED24") (pin "K") (pinfunction "C_K") (pintype "passive"))
      (node (ref "LED32") (pin "K") (pinfunction "C_K") (pintype "passive"))
      (node (ref "U$10") (pin "3") (pinfunction "3_3") (pintype "bidirectional"))
      (node (ref "U$13") (pin "3") (pinfunction "3_3") (pintype "bidirectional"))
      (node (ref "U$8") (pin "7") (pinfunction "7_7") (pintype "bidirectional"))
      (node (ref "U$9") (pin "5") (pinfunction "5_5") (pintype "bidirectional"))
    )
    (net (code "34") (name "GPOINSIDE8") (class "Default")
      (node (ref "IC1") (pin "11") (pinfunction "O8_11") (pintype "open_collector"))
      (node (ref "K8") (pin "16") (pinfunction "2_16") (pintype "passive"))
      (node (ref "LED25") (pin "K") (pinfunction "C_K") (pintype "passive"))
      (node (ref "LED33") (pin "K") (pinfunction "C_K") (pintype "passive"))
      (node (ref "U$10") (pin "4") (pinfunction "4_4") (pintype "bidirectional"))
      (node (ref "U$13") (pin "5") (pinfunction "5_5") (pintype "bidirectional"))
      (node (ref "U$8") (pin "8") (pinfunction "8_8") (pintype "bidirectional"))
      (node (ref "U$9") (pin "6") (pinfunction "6_6") (pintype "bidirectional"))
    )
    (net (code "35") (name "I2C_SCL") (class "Default")
      (node (ref "IC2") (pin "12") (pinfunction "SCL_12") (pintype "input"))
      (node (ref "JP4") (pin "2") (pinfunction "2_2") (pintype "passive"))
      (node (ref "R2") (pin "1") (pinfunction "1_1") (pintype "passive"))
      (node (ref "SERIAL") (pin "4") (pinfunction "4_4") (pintype "passive"))
    )
    (net (code "36") (name "I2C_SDA") (class "Default")
      (node (ref "IC2") (pin "13") (pinfunction "SDA_13") (pintype "bidirectional"))
      (node (ref "JP4") (pin "1") (pinfunction "1_1") (pintype "passive"))
      (node (ref "R1") (pin "1") (pinfunction "1_1") (pintype "passive"))
      (node (ref "SERIAL") (pin "3") (pinfunction "3_3") (pintype "passive"))
    )
    (net (code "37") (name "IN1") (class "Default")
      (node (ref "IC2") (pin "21") (pinfunction "GPA0_21") (pintype "bidirectional"))
      (node (ref "LED1") (pin "K") (pinfunction "C_K") (pintype "passive"))
      (node (ref "OK1") (pin "8") (pinfunction "COL_8") (pintype "passive"))
    )
    (net (code "38") (name "IN2") (class "Default")
      (node (ref "IC2") (pin "22") (pinfunction "GPA1_22") (pintype "bidirectional"))
      (node (ref "LED2") (pin "K") (pinfunction "C_K") (pintype "passive"))
      (node (ref "OK1") (pin "6") (pinfunction "COL_6") (pintype "passive"))
    )
    (net (code "39") (name "IN3") (class "Default")
      (node (ref "IC2") (pin "23") (pinfunction "GPA2_23") (pintype "bidirectional"))
      (node (ref "LED3") (pin "K") (pinfunction "C_K") (pintype "passive"))
      (node (ref "OK2") (pin "8") (pinfunction "COL_8") (pintype "passive"))
    )
    (net (code "40") (name "IN4") (class "Default")
      (node (ref "IC2") (pin "24") (pinfunction "GPA3_24") (pintype "bidirectional"))
      (node (ref "LED4") (pin "K") (pinfunction "C_K") (pintype "passive"))
      (node (ref "OK2") (pin "6") (pinfunction "COL_6") (pintype "passive"))
    )
    (net (code "41") (name "IN5") (class "Default")
      (node (ref "IC2") (pin "25") (pinfunction "GPA4_25") (pintype "bidirectional"))
      (node (ref "LED5") (pin "K") (pinfunction "C_K") (pintype "passive"))
      (node (ref "OK3") (pin "8") (pinfunction "COL_8") (pintype "passive"))
    )
    (net (code "42") (name "IN6") (class "Default")
      (node (ref "IC2") (pin "26") (pinfunction "GPA5_26") (pintype "bidirectional"))
      (node (ref "LED6") (pin "K") (pinfunction "C_K") (pintype "passive"))
      (node (ref "OK3") (pin "6") (pinfunction "COL_6") (pintype "passive"))
    )
    (net (code "43") (name "IN7") (class "Default")
      (node (ref "IC2") (pin "27") (pinfunction "GPA6_27") (pintype "bidirectional"))
      (node (ref "LED7") (pin "K") (pinfunction "C_K") (pintype "passive"))
      (node (ref "OK4") (pin "8") (pinfunction "COL_8") (pintype "passive"))
    )
    (net (code "44") (name "IN8") (class "Default")
      (node (ref "IC2") (pin "28") (pinfunction "GPA7_28") (pintype "bidirectional"))
      (node (ref "LED8") (pin "K") (pinfunction "C_K") (pintype "passive"))
      (node (ref "OK4") (pin "6") (pinfunction "COL_6") (pintype "passive"))
    )
    (net (code "45") (name "Net-(IC1-I1)") (class "Default")
      (node (ref "IC1") (pin "1") (pinfunction "I1_1") (pintype "input"))
      (node (ref "IC2") (pin "1") (pinfunction "GPB0_1") (pintype "bidirectional"))
    )
    (net (code "46") (name "Net-(IC1-I2)") (class "Default")
      (node (ref "IC1") (pin "2") (pinfunction "I2_2") (pintype "input"))
      (node (ref "IC2") (pin "2") (pinfunction "GPB1_2") (pintype "bidirectional"))
    )
    (net (code "47") (name "Net-(IC1-I3)") (class "Default")
      (node (ref "IC1") (pin "3") (pinfunction "I3_3") (pintype "input"))
      (node (ref "IC2") (pin "3") (pinfunction "GPB2_3") (pintype "bidirectional"))
    )
    (net (code "48") (name "Net-(IC1-I4)") (class "Default")
      (node (ref "IC1") (pin "4") (pinfunction "I4_4") (pintype "input"))
      (node (ref "IC2") (pin "4") (pinfunction "GPB3_4") (pintype "bidirectional"))
    )
    (net (code "49") (name "Net-(IC1-I5)") (class "Default")
      (node (ref "IC1") (pin "5") (pinfunction "I5_5") (pintype "input"))
      (node (ref "IC2") (pin "5") (pinfunction "GPB4_5") (pintype "bidirectional"))
    )
    (net (code "50") (name "Net-(IC1-I6)") (class "Default")
      (node (ref "IC1") (pin "6") (pinfunction "I6_6") (pintype "input"))
      (node (ref "IC2") (pin "6") (pinfunction "GPB5_6") (pintype "bidirectional"))
    )
    (net (code "51") (name "Net-(IC1-I7)") (class "Default")
      (node (ref "IC1") (pin "7") (pinfunction "I7_7") (pintype "input"))
      (node (ref "IC2") (pin "7") (pinfunction "GPB6_7") (pintype "bidirectional"))
    )
    (net (code "52") (name "Net-(IC1-I8)") (class "Default")
      (node (ref "IC1") (pin "8") (pinfunction "I8_8") (pintype "input"))
      (node (ref "IC2") (pin "8") (pinfunction "GPB7_8") (pintype "bidirectional"))
    )
    (net (code "53") (name "Net-(JP3-Pad2)") (class "Default")
      (node (ref "JP3") (pin "2") (pinfunction "2_2") (pintype "passive"))
      (node (ref "JP5") (pin "2") (pinfunction "2_2") (pintype "passive"))
    )
    (net (code "54") (name "Net-(JP3-Pad4)") (class "Default")
      (node (ref "JP3") (pin "4") (pinfunction "4_4") (pintype "passive"))
      (node (ref "JP5") (pin "4") (pinfunction "4_4") (pintype "passive"))
    )
    (net (code "55") (name "Net-(JP3-Pad5)") (class "Default")
      (node (ref "JP3") (pin "5") (pinfunction "5_5") (pintype "passive"))
      (node (ref "JP5") (pin "5") (pinfunction "5_5") (pintype "passive"))
    )
    (net (code "56") (name "Net-(JP3-Pad6)") (class "Default")
      (node (ref "JP3") (pin "6") (pinfunction "6_6") (pintype "passive"))
      (node (ref "JP5") (pin "6") (pinfunction "6_6") (pintype "passive"))
    )
    (net (code "57") (name "Net-(LED1-PadA)") (class "Default")
      (node (ref "LED1") (pin "A") (pinfunction "A_A") (pintype "passive"))
      (node (ref "RN1") (pin "2") (pinfunction "2_2") (pintype "passive"))
    )
    (net (code "58") (name "Net-(LED2-PadA)") (class "Default")
      (node (ref "LED2") (pin "A") (pinfunction "A_A") (pintype "passive"))
      (node (ref "RN1") (pin "3") (pinfunction "3_3") (pintype "passive"))
    )
    (net (code "59") (name "Net-(LED3-PadA)") (class "Default")
      (node (ref "LED3") (pin "A") (pinfunction "A_A") (pintype "passive"))
      (node (ref "RN1") (pin "4") (pinfunction "4_4") (pintype "passive"))
    )
    (net (code "60") (name "Net-(LED4-PadA)") (class "Default")
      (node (ref "LED4") (pin "A") (pinfunction "A_A") (pintype "passive"))
      (node (ref "RN1") (pin "5") (pinfunction "5_5") (pintype "passive"))
    )
    (net (code "61") (name "Net-(LED5-PadA)") (class "Default")
      (node (ref "LED5") (pin "A") (pinfunction "A_A") (pintype "passive"))
      (node (ref "RN1") (pin "6") (pinfunction "6_6") (pintype "passive"))
    )
    (net (code "62") (name "Net-(LED6-PadA)") (class "Default")
      (node (ref "LED6") (pin "A") (pinfunction "A_A") (pintype "passive"))
      (node (ref "RN1") (pin "7") (pinfunction "7_7") (pintype "passive"))
    )
    (net (code "63") (name "Net-(LED7-PadA)") (class "Default")
      (node (ref "LED7") (pin "A") (pinfunction "A_A") (pintype "passive"))
      (node (ref "RN1") (pin "8") (pinfunction "8_8") (pintype "passive"))
    )
    (net (code "64") (name "Net-(LED8-PadA)") (class "Default")
      (node (ref "LED8") (pin "A") (pinfunction "A_A") (pintype "passive"))
      (node (ref "RN1") (pin "9") (pinfunction "9_9") (pintype "passive"))
    )
    (net (code "65") (name "Net-(LED9-PadA)") (class "Default")
      (node (ref "LED9") (pin "A") (pinfunction "A_A") (pintype "passive"))
      (node (ref "RN2") (pin "2") (pinfunction "2_2") (pintype "passive"))
    )
    (net (code "66") (name "Net-(LED10-PadA)") (class "Default")
      (node (ref "LED10") (pin "A") (pinfunction "A_A") (pintype "passive"))
      (node (ref "RN2") (pin "3") (pinfunction "3_3") (pintype "passive"))
    )
    (net (code "67") (name "Net-(LED11-PadA)") (class "Default")
      (node (ref "LED11") (pin "A") (pinfunction "A_A") (pintype "passive"))
      (node (ref "RN2") (pin "4") (pinfunction "4_4") (pintype "passive"))
    )
    (net (code "68") (name "Net-(LED12-PadA)") (class "Default")
      (node (ref "LED12") (pin "A") (pinfunction "A_A") (pintype "passive"))
      (node (ref "RN2") (pin "5") (pinfunction "5_5") (pintype "passive"))
    )
    (net (code "69") (name "Net-(LED13-PadA)") (class "Default")
      (node (ref "LED13") (pin "A") (pinfunction "A_A") (pintype "passive"))
      (node (ref "RN2") (pin "6") (pinfunction "6_6") (pintype "passive"))
    )
    (net (code "70") (name "Net-(LED14-PadA)") (class "Default")
      (node (ref "LED14") (pin "A") (pinfunction "A_A") (pintype "passive"))
      (node (ref "RN2") (pin "7") (pinfunction "7_7") (pintype "passive"))
    )
    (net (code "71") (name "Net-(LED15-PadA)") (class "Default")
      (node (ref "LED15") (pin "A") (pinfunction "A_A") (pintype "passive"))
      (node (ref "RN2") (pin "8") (pinfunction "8_8") (pintype "passive"))
    )
    (net (code "72") (name "Net-(LED16-PadA)") (class "Default")
      (node (ref "LED16") (pin "A") (pinfunction "A_A") (pintype "passive"))
      (node (ref "RN2") (pin "9") (pinfunction "9_9") (pintype "passive"))
    )
    (net (code "73") (name "Net-(LED17-PadA)") (class "Default")
      (node (ref "LED17") (pin "A") (pinfunction "A_A") (pintype "passive"))
      (node (ref "R5") (pin "1") (pinfunction "1_1") (pintype "passive"))
    )
    (net (code "74") (name "Net-(LED18-PadA)") (class "Default")
      (node (ref "LED18") (pin "A") (pinfunction "A_A") (pintype "passive"))
      (node (ref "RN5") (pin "2") (pinfunction "2_2") (pintype "passive"))
    )
    (net (code "75") (name "Net-(LED19-PadA)") (class "Default")
      (node (ref "LED19") (pin "A") (pinfunction "A_A") (pintype "passive"))
      (node (ref "RN5") (pin "3") (pinfunction "3_3") (pintype "passive"))
    )
    (net (code "76") (name "Net-(LED20-PadA)") (class "Default")
      (node (ref "LED20") (pin "A") (pinfunction "A_A") (pintype "passive"))
      (node (ref "RN5") (pin "4") (pinfunction "4_4") (pintype "passive"))
    )
    (net (code "77") (name "Net-(LED21-PadA)") (class "Default")
      (node (ref "LED21") (pin "A") (pinfunction "A_A") (pintype "passive"))
      (node (ref "RN5") (pin "5") (pinfunction "5_5") (pintype "passive"))
    )
    (net (code "78") (name "Net-(LED22-PadA)") (class "Default")
      (node (ref "LED22") (pin "A") (pinfunction "A_A") (pintype "passive"))
      (node (ref "RN5") (pin "6") (pinfunction "6_6") (pintype "passive"))
    )
    (net (code "79") (name "Net-(LED23-PadA)") (class "Default")
      (node (ref "LED23") (pin "A") (pinfunction "A_A") (pintype "passive"))
      (node (ref "RN5") (pin "7") (pinfunction "7_7") (pintype "passive"))
    )
    (net (code "80") (name "Net-(LED24-PadA)") (class "Default")
      (node (ref "LED24") (pin "A") (pinfunction "A_A") (pintype "passive"))
      (node (ref "RN5") (pin "8") (pinfunction "8_8") (pintype "passive"))
    )
    (net (code "81") (name "Net-(LED25-PadA)") (class "Default")
      (node (ref "LED25") (pin "A") (pinfunction "A_A") (pintype "passive"))
      (node (ref "RN5") (pin "9") (pinfunction "9_9") (pintype "passive"))
    )
    (net (code "82") (name "Net-(LED26-PadA)") (class "Default")
      (node (ref "LED26") (pin "A") (pinfunction "A_A") (pintype "passive"))
      (node (ref "RN4") (pin "2") (pinfunction "2_2") (pintype "passive"))
    )
    (net (code "83") (name "Net-(LED27-PadA)") (class "Default")
      (node (ref "LED27") (pin "A") (pinfunction "A_A") (pintype "passive"))
      (node (ref "RN4") (pin "3") (pinfunction "3_3") (pintype "passive"))
    )
    (net (code "84") (name "Net-(LED28-PadA)") (class "Default")
      (node (ref "LED28") (pin "A") (pinfunction "A_A") (pintype "passive"))
      (node (ref "RN4") (pin "4") (pinfunction "4_4") (pintype "passive"))
    )
    (net (code "85") (name "Net-(LED29-PadA)") (class "Default")
      (node (ref "LED29") (pin "A") (pinfunction "A_A") (pintype "passive"))
      (node (ref "RN4") (pin "5") (pinfunction "5_5") (pintype "passive"))
    )
    (net (code "86") (name "Net-(LED30-PadA)") (class "Default")
      (node (ref "LED30") (pin "A") (pinfunction "A_A") (pintype "passive"))
      (node (ref "RN4") (pin "6") (pinfunction "6_6") (pintype "passive"))
    )
    (net (code "87") (name "Net-(LED31-PadA)") (class "Default")
      (node (ref "LED31") (pin "A") (pinfunction "A_A") (pintype "passive"))
      (node (ref "RN4") (pin "7") (pinfunction "7_7") (pintype "passive"))
    )
    (net (code "88") (name "Net-(LED32-PadA)") (class "Default")
      (node (ref "LED32") (pin "A") (pinfunction "A_A") (pintype "passive"))
      (node (ref "RN4") (pin "8") (pinfunction "8_8") (pintype "passive"))
    )
    (net (code "89") (name "Net-(LED33-PadA)") (class "Default")
      (node (ref "LED33") (pin "A") (pinfunction "A_A") (pintype "passive"))
      (node (ref "RN4") (pin "9") (pinfunction "9_9") (pintype "passive"))
    )
    (net (code "90") (name "Net-(OK1A-A)") (class "Default")
      (node (ref "OK1") (pin "1") (pinfunction "A_1") (pintype "passive"))
      (node (ref "RN3") (pin "2") (pinfunction "2_2") (pintype "passive"))
    )
    (net (code "91") (name "Net-(OK1B-A)") (class "Default")
      (node (ref "OK1") (pin "3") (pinfunction "A_3") (pintype "passive"))
      (node (ref "RN3") (pin "3") (pinfunction "3_3") (pintype "passive"))
    )
    (net (code "92") (name "Net-(OK2A-A)") (class "Default")
      (node (ref "OK2") (pin "1") (pinfunction "A_1") (pintype "passive"))
      (node (ref "RN3") (pin "4") (pinfunction "4_4") (pintype "passive"))
    )
    (net (code "93") (name "Net-(OK2B-A)") (class "Default")
      (node (ref "OK2") (pin "3") (pinfunction "A_3") (pintype "passive"))
      (node (ref "RN3") (pin "5") (pinfunction "5_5") (pintype "passive"))
    )
    (net (code "94") (name "Net-(OK3A-A)") (class "Default")
      (node (ref "OK3") (pin "1") (pinfunction "A_1") (pintype "passive"))
      (node (ref "RN3") (pin "6") (pinfunction "6_6") (pintype "passive"))
    )
    (net (code "95") (name "Net-(OK3B-A)") (class "Default")
      (node (ref "OK3") (pin "3") (pinfunction "A_3") (pintype "passive"))
      (node (ref "RN3") (pin "7") (pinfunction "7_7") (pintype "passive"))
    )
    (net (code "96") (name "Net-(OK4A-A)") (class "Default")
      (node (ref "OK4") (pin "1") (pinfunction "A_1") (pintype "passive"))
      (node (ref "RN3") (pin "8") (pinfunction "8_8") (pintype "passive"))
    )
    (net (code "97") (name "Net-(OK4B-A)") (class "Default")
      (node (ref "OK4") (pin "3") (pinfunction "A_3") (pintype "passive"))
      (node (ref "RN3") (pin "9") (pinfunction "9_9") (pintype "passive"))
    )
    (net (code "98") (name "Net-(U$7-P$2)") (class "Default")
      (node (ref "R4") (pin "1") (pinfunction "1_1") (pintype "passive"))
      (node (ref "U$7") (pin "A2") (pinfunction "P$2_A2") (pintype "bidirectional"))
    )
    (net (code "99") (name "Net-(U$7-P$3)") (class "Default")
      (node (ref "R3") (pin "1") (pinfunction "1_1") (pintype "passive"))
      (node (ref "U$7") (pin "A3") (pinfunction "P$3_A3") (pintype "bidirectional"))
    )
    (net (code "100") (name "O1") (class "Default")
      (node (ref "K1") (pin "S2") (pinfunction "S_S2") (pintype "passive"))
      (node (ref "LED9") (pin "K") (pinfunction "C_K") (pintype "passive"))
    )
    (net (code "101") (name "O2") (class "Default")
      (node (ref "K2") (pin "S2") (pinfunction "S_S2") (pintype "passive"))
      (node (ref "LED10") (pin "K") (pinfunction "C_K") (pintype "passive"))
    )
    (net (code "102") (name "O3") (class "Default")
      (node (ref "K3") (pin "S2") (pinfunction "S_S2") (pintype "passive"))
      (node (ref "LED11") (pin "K") (pinfunction "C_K") (pintype "passive"))
    )
    (net (code "103") (name "O4") (class "Default")
      (node (ref "K4") (pin "S2") (pinfunction "S_S2") (pintype "passive"))
      (node (ref "LED12") (pin "K") (pinfunction "C_K") (pintype "passive"))
    )
    (net (code "104") (name "O5") (class "Default")
      (node (ref "K5") (pin "S2") (pinfunction "S_S2") (pintype "passive"))
      (node (ref "LED13") (pin "K") (pinfunction "C_K") (pintype "passive"))
    )
    (net (code "105") (name "O6") (class "Default")
      (node (ref "K6") (pin "S2") (pinfunction "S_S2") (pintype "passive"))
      (node (ref "LED14") (pin "K") (pinfunction "C_K") (pintype "passive"))
    )
    (net (code "106") (name "O7") (class "Default")
      (node (ref "K7") (pin "S2") (pinfunction "S_S2") (pintype "passive"))
      (node (ref "LED15") (pin "K") (pinfunction "C_K") (pintype "passive"))
    )
    (net (code "107") (name "O8") (class "Default")
      (node (ref "K8") (pin "S2") (pinfunction "S_S2") (pintype "passive"))
      (node (ref "LED16") (pin "K") (pinfunction "C_K") (pintype "passive"))
    )
    (net (code "108") (name "RES") (class "Default")
      (node (ref "GND") (pin "RES") (pinfunction "RES_RES") (pintype "bidirectional"))
      (node (ref "RESETA") (pin "1") (pinfunction "1_1") (pintype "passive"))
    )
    (net (code "109") (name "SDI_MOSI") (class "Default")
      (node (ref "SERIAL") (pin "8") (pinfunction "8_8") (pintype "passive"))
    )
    (net (code "110") (name "SDI_SCLK") (class "Default")
      (node (ref "SERIAL") (pin "7") (pinfunction "7_7") (pintype "passive"))
    )
    (net (code "111") (name "SLIDER_IN") (class "Default")
      (node (ref "GND") (pin "A0") (pinfunction "A0_A0") (pintype "bidirectional"))
      (node (ref "SERIAL") (pin "5") (pinfunction "5_5") (pintype "passive"))
    )
    (net (code "112") (name "VIN") (class "Default")
      (node (ref "GND") (pin "VIN") (pinfunction "VIN_VIN") (pintype "bidirectional"))
    )
    (net (code "113") (name "unconnected-(GND-*D5-PadD5)") (class "Default")
      (node (ref "GND") (pin "D5") (pinfunction "*D5_D5") (pintype "bidirectional"))
    )
    (net (code "114") (name "unconnected-(GND-*D6-PadD6)") (class "Default")
      (node (ref "GND") (pin "D6") (pinfunction "*D6_D6") (pintype "bidirectional"))
    )
    (net (code "115") (name "unconnected-(GND-*D9-PadD9)") (class "Default")
      (node (ref "GND") (pin "D9") (pinfunction "*D9_D9") (pintype "bidirectional"))
    )
    (net (code "116") (name "unconnected-(GND-*D10-PadD10)") (class "Default")
      (node (ref "GND") (pin "D10") (pinfunction "*D10_D10") (pintype "bidirectional"))
    )
    (net (code "117") (name "unconnected-(GND-*D11-PadD11)") (class "Default")
      (node (ref "GND") (pin "D11") (pinfunction "*D11_D11") (pintype "bidirectional"))
    )
    (net (code "118") (name "unconnected-(GND-Pad3.3V)") (class "Default")
      (node (ref "GND") (pin "3.3V") (pinfunction "3.3V_3.3V") (pintype "bidirectional"))
    )
    (net (code "119") (name "unconnected-(GND-PadA2)") (class "Default")
      (node (ref "GND") (pin "A2") (pinfunction "A2_A2") (pintype "bidirectional"))
    )
    (net (code "120") (name "unconnected-(GND-PadA3)") (class "Default")
      (node (ref "GND") (pin "A3") (pinfunction "A3_A3") (pintype "bidirectional"))
    )
    (net (code "121") (name "unconnected-(GND-PadA4)") (class "Default")
      (node (ref "GND") (pin "A4") (pinfunction "A4_A4") (pintype "bidirectional"))
    )
    (net (code "122") (name "unconnected-(GND-PadA5)") (class "Default")
      (node (ref "GND") (pin "A5") (pinfunction "A5_A5") (pintype "bidirectional"))
    )
    (net (code "123") (name "unconnected-(GND-PadAREF)") (class "Default")
      (node (ref "GND") (pin "AREF") (pinfunction "AREF_AREF") (pintype "bidirectional"))
    )
    (net (code "124") (name "unconnected-(GND-PadD4)") (class "Default")
      (node (ref "GND") (pin "D4") (pinfunction "D4_D4") (pintype "bidirectional"))
    )
    (net (code "125") (name "unconnected-(GND-PadD8)") (class "Default")
      (node (ref "GND") (pin "D8") (pinfunction "D8_D8") (pintype "bidirectional"))
    )
    (net (code "126") (name "unconnected-(GND-PadD12)") (class "Default")
      (node (ref "GND") (pin "D12") (pinfunction "D12_D12") (pintype "bidirectional"))
    )
    (net (code "127") (name "unconnected-(GND-PadD13)") (class "Default")
      (node (ref "GND") (pin "D13") (pinfunction "D13_D13") (pintype "bidirectional"))
    )
    (net (code "128") (name "unconnected-(GND-PadRX)") (class "Default")
      (node (ref "GND") (pin "RX") (pinfunction "RX_RX") (pintype "bidirectional"))
    )
    (net (code "129") (name "unconnected-(GND-PadTX)") (class "Default")
      (node (ref "GND") (pin "TX") (pinfunction "TX_TX") (pintype "bidirectional"))
    )
    (net (code "130") (name "unconnected-(IC2-INTA-Pad20)") (class "Default")
      (node (ref "IC2") (pin "20") (pinfunction "INTA_20") (pintype "output"))
    )
    (net (code "131") (name "unconnected-(IC2-INTB-Pad19)") (class "Default")
      (node (ref "IC2") (pin "19") (pinfunction "INTB_19") (pintype "output"))
    )
    (net (code "132") (name "unconnected-(JP1-Pad1)") (class "Default")
      (node (ref "JP1") (pin "1") (pinfunction "1_1") (pintype "passive"))
    )
    (net (code "133") (name "unconnected-(JP1-Pad2)") (class "Default")
      (node (ref "JP1") (pin "2") (pinfunction "2_2") (pintype "passive"))
    )
    (net (code "134") (name "unconnected-(K1B-O-PadO1)") (class "Default")
      (node (ref "K1") (pin "O1") (pinfunction "O_O1") (pintype "passive"))
    )
    (net (code "135") (name "unconnected-(K1C-O-PadO2)") (class "Default")
      (node (ref "K1") (pin "O2") (pinfunction "O_O2") (pintype "passive"))
    )
    (net (code "136") (name "unconnected-(K2B-O-PadO1)") (class "Default")
      (node (ref "K2") (pin "O1") (pinfunction "O_O1") (pintype "passive"))
    )
    (net (code "137") (name "unconnected-(K2C-O-PadO2)") (class "Default")
      (node (ref "K2") (pin "O2") (pinfunction "O_O2") (pintype "passive"))
    )
    (net (code "138") (name "unconnected-(K3B-O-PadO1)") (class "Default")
      (node (ref "K3") (pin "O1") (pinfunction "O_O1") (pintype "passive"))
    )
    (net (code "139") (name "unconnected-(K3C-O-PadO2)") (class "Default")
      (node (ref "K3") (pin "O2") (pinfunction "O_O2") (pintype "passive"))
    )
    (net (code "140") (name "unconnected-(K4B-O-PadO1)") (class "Default")
      (node (ref "K4") (pin "O1") (pinfunction "O_O1") (pintype "passive"))
    )
    (net (code "141") (name "unconnected-(K4C-O-PadO2)") (class "Default")
      (node (ref "K4") (pin "O2") (pinfunction "O_O2") (pintype "passive"))
    )
    (net (code "142") (name "unconnected-(K5B-O-PadO1)") (class "Default")
      (node (ref "K5") (pin "O1") (pinfunction "O_O1") (pintype "passive"))
    )
    (net (code "143") (name "unconnected-(K5C-O-PadO2)") (class "Default")
      (node (ref "K5") (pin "O2") (pinfunction "O_O2") (pintype "passive"))
    )
    (net (code "144") (name "unconnected-(K6B-O-PadO1)") (class "Default")
      (node (ref "K6") (pin "O1") (pinfunction "O_O1") (pintype "passive"))
    )
    (net (code "145") (name "unconnected-(K6C-O-PadO2)") (class "Default")
      (node (ref "K6") (pin "O2") (pinfunction "O_O2") (pintype "passive"))
    )
    (net (code "146") (name "unconnected-(K7B-O-PadO1)") (class "Default")
      (node (ref "K7") (pin "O1") (pinfunction "O_O1") (pintype "passive"))
    )
    (net (code "147") (name "unconnected-(K7C-O-PadO2)") (class "Default")
      (node (ref "K7") (pin "O2") (pinfunction "O_O2") (pintype "passive"))
    )
    (net (code "148") (name "unconnected-(K8B-O-PadO1)") (class "Default")
      (node (ref "K8") (pin "O1") (pinfunction "O_O1") (pintype "passive"))
    )
    (net (code "149") (name "unconnected-(K8C-O-PadO2)") (class "Default")
      (node (ref "K8") (pin "O2") (pinfunction "O_O2") (pintype "passive"))
    )
    (net (code "150") (name "unconnected-(U$11-Pad4)") (class "Default")
      (node (ref "U$11") (pin "4") (pinfunction "4_4") (pintype "bidirectional"))
    )
    (net (code "151") (name "unconnected-(U$11-Pad6)") (class "Default")
      (node (ref "U$11") (pin "6") (pinfunction "6_6") (pintype "bidirectional"))
    )
    (net (code "152") (name "unconnected-(U$11-Pad8)") (class "Default")
      (node (ref "U$11") (pin "8") (pinfunction "8_8") (pintype "bidirectional"))
    )
    (net (code "153") (name "unconnected-(U$12-Pad4)") (class "Default")
      (node (ref "U$12") (pin "4") (pinfunction "4_4") (pintype "bidirectional"))
    )
    (net (code "154") (name "unconnected-(U$12-Pad6)") (class "Default")
      (node (ref "U$12") (pin "6") (pinfunction "6_6") (pintype "bidirectional"))
    )
    (net (code "155") (name "unconnected-(U$12-Pad8)") (class "Default")
      (node (ref "U$12") (pin "8") (pinfunction "8_8") (pintype "bidirectional"))
    )
    (net (code "156") (name "unconnected-(U$13-Pad4)") (class "Default")
      (node (ref "U$13") (pin "4") (pinfunction "4_4") (pintype "bidirectional"))
    )
    (net (code "157") (name "unconnected-(U$13-Pad6)") (class "Default")
      (node (ref "U$13") (pin "6") (pinfunction "6_6") (pintype "bidirectional"))
    )
    (net (code "158") (name "unconnected-(U$13-Pad7)") (class "Default")
      (node (ref "U$13") (pin "7") (pinfunction "7_7") (pintype "bidirectional"))
    )
    (net (code "159") (name "unconnected-(U$13-Pad8)") (class "Default")
      (node (ref "U$13") (pin "8") (pinfunction "8_8") (pintype "bidirectional"))
    )
  )
)
